# Color_Sensor.net
KiCad netlist of a schematic drawn in Altium Designer
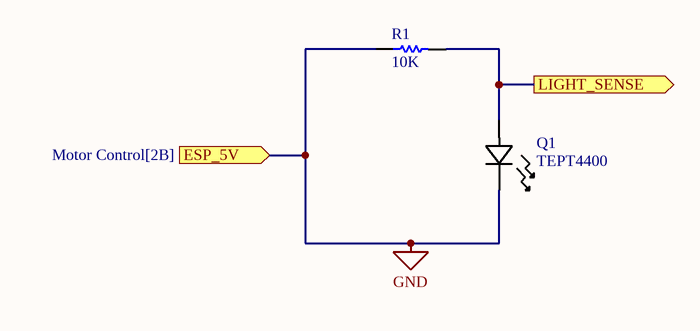
[diagram p0: Color_Sensor.SchDoc]

(export (version "E")
  (design (tool "Eeschema 10.0.6"))
  (components
    (comp (ref "Q1")
      (value "TEPT4400")
      (footprint "LED_TEPT4400_VIS")
      (description "PHOTO TRANS. 3MM  30DEG-e4")
      (fields (field (name "COPYRIGHT") "Copyright (C) 2026 Ultra Librarian. All rights reserved."))
      (libsource (lib "TEPT4400") (part "TEPT4400"))
    )
    (comp (ref "R1")
      (value "10K")
      (description "Resistor")
      (libsource (lib "Simulation Generic Components") (part "Resistor"))
    )
  )
  (nets
    (net (code "1") (name "/LIGHT_SENSE") (class "Default")
      (node (ref "Q1") (pin "2") (pinfunction "2_2") (pintype "passive"))
      (node (ref "R1") (pin "2") (pinfunction "2_2") (pintype "passive"))
    )
    (net (code "2") (name "GND") (class "Default")
      (node (ref "Q1") (pin "1") (pinfunction "1_1") (pintype "passive"))
      (node (ref "R1") (pin "1") (pinfunction "1_1") (pintype "passive"))
    )
  )
)
